# tank_adapter.net
KiCad netlist of a schematic drawn in Altium Designer
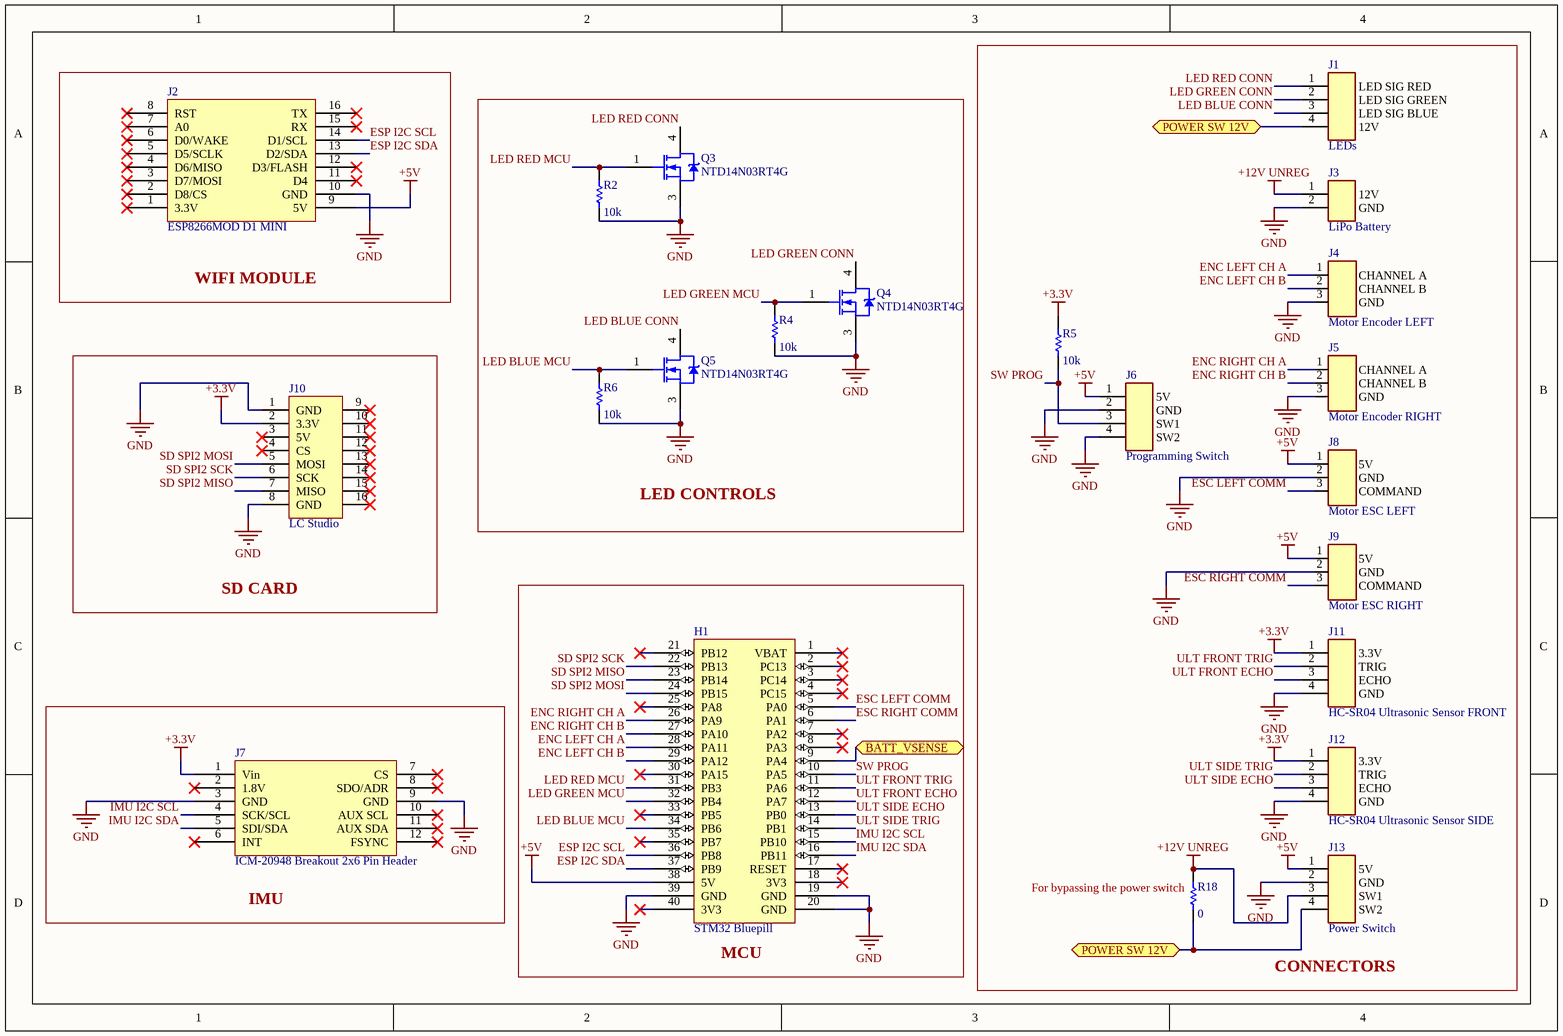
[diagram p0: tank_adapter.SchDoc]

(export (version "E")
  (design (tool "Eeschema 10.0.6"))
  (components
    (comp (ref "H1")
      (value "STM32 Bluepill")
      (footprint "STM32 Bluepill")
      (libsource (lib "Cell_Tester") (part "STM32 Bluepill"))
    )
    (comp (ref "J1")
      (value "LEDs")
      (footprint "HDRV4W85P254_4X1_1062X650X1000")
      (description "4 Position Wire to Board Terminal Block Horizontal with Board 0.100 _2.54mm_ Through Hole")
      (fields (field (name "MF") "TE Connectivity") (field (name "MP") "282834-4"))
      (libsource (lib "282834-4-1") (part "282834-4"))
    )
    (comp (ref "J2")
      (value "ESP8266MOD D1 MINI")
      (footprint "ESP8266MOD D1 MINI")
      (libsource (lib "MTE380_Lib") (part "ESP8266MOD D1 MINI"))
    )
    (comp (ref "J3")
      (value "LiPo Battery")
      (footprint "TE_282837-2")
      (description "Connector Terminal Blocks Receptacle 2 Position 5.08mm Solder Straight Thru-Hole 13.5A/Contact")
      (fields (field (name "MF") "TE Connectivity") (field (name "MP") "282837-2"))
      (libsource (lib "282837-2") (part "282837-2"))
    )
    (comp (ref "J4")
      (value "Motor Encoder LEFT")
      (footprint "TE_282834-3")
      (description "3 Position Wire to Board Terminal Block Horizontal with Board 0.100 (2.54mm)")
      (fields (field (name "MF") "TE Connectivity") (field (name "MP") "282834-3"))
      (libsource (lib "282834-3") (part "282834-3"))
    )
    (comp (ref "J5")
      (value "Motor Encoder RIGHT")
      (footprint "TE_282834-3")
      (description "3 Position Wire to Board Terminal Block Horizontal with Board 0.100 (2.54mm)")
      (fields (field (name "MF") "TE Connectivity") (field (name "MP") "282834-3"))
      (libsource (lib "282834-3") (part "282834-3"))
    )
    (comp (ref "J6")
      (value "Programming Switch")
      (footprint "HDRV4W85P254_4X1_1062X650X1000")
      (description "4 Position Wire to Board Terminal Block Horizontal with Board 0.100 _2.54mm_ Through Hole")
      (fields (field (name "MF") "TE Connectivity") (field (name "MP") "282834-4"))
      (libsource (lib "282834-4-1") (part "282834-4"))
    )
    (comp (ref "J7")
      (value "ICM-20948 Breakout 2x6 Pin Header")
      (footprint "ICM20948 Breakout")
      (description "THT Vertical Pin Header WR-PHD, Pitch 2.54 mm, Double Row, 2x6 pins")
      (libsource (lib "MTE380_Lib") (part "ICM-20948 Breakout 2x6 Pin Header"))
    )
    (comp (ref "J8")
      (value "Motor ESC LEFT")
      (footprint "TE_282834-3")
      (description "3 Position Wire to Board Terminal Block Horizontal with Board 0.100 (2.54mm)")
      (fields (field (name "MF") "TE Connectivity") (field (name "MP") "282834-3"))
      (libsource (lib "282834-3") (part "282834-3"))
    )
    (comp (ref "J9")
      (value "Motor ESC RIGHT")
      (footprint "TE_282834-3")
      (description "3 Position Wire to Board Terminal Block Horizontal with Board 0.100 (2.54mm)")
      (fields (field (name "MF") "TE Connectivity") (field (name "MP") "282834-3"))
      (libsource (lib "282834-3") (part "282834-3"))
    )
    (comp (ref "J10")
      (value "LC Studio")
      (footprint "HDR2X8_CEN")
      (description "Header, 8-Pin, Dual row")
      (fields (field (name "PUBLISHER") "Altium Limited"))
      (libsource (lib "Miscellaneous Connectors") (part "Header 8X2A"))
    )
    (comp (ref "J11")
      (value "HC-SR04 Ultrasonic Sensor FRONT")
      (footprint "HDRV4W85P254_4X1_1062X650X1000")
      (description "4 Position Wire to Board Terminal Block Horizontal with Board 0.100 _2.54mm_ Through Hole")
      (fields (field (name "MF") "TE Connectivity") (field (name "MP") "282834-4"))
      (libsource (lib "282834-4-1") (part "282834-4"))
    )
    (comp (ref "J12")
      (value "HC-SR04 Ultrasonic Sensor SIDE")
      (footprint "HDRV4W85P254_4X1_1062X650X1000")
      (description "4 Position Wire to Board Terminal Block Horizontal with Board 0.100 _2.54mm_ Through Hole")
      (fields (field (name "MF") "TE Connectivity") (field (name "MP") "282834-4"))
      (libsource (lib "282834-4-1") (part "282834-4"))
    )
    (comp (ref "J13")
      (value "Power Switch")
      (footprint "HDRV4W85P254_4X1_1062X650X1000")
      (description "4 Position Wire to Board Terminal Block Horizontal with Board 0.100 _2.54mm_ Through Hole")
      (fields (field (name "MF") "TE Connectivity") (field (name "MP") "282834-4"))
      (libsource (lib "282834-4-1") (part "282834-4"))
    )
    (comp (ref "Q3")
      (value "NTD14N03RT4G")
      (footprint "ONSC-DPAK-3-369C-01_V")
      (description "Power MOSFET, 14 A, 25 V, N-Channel, 3-Pin DPAK, Pb-Free, Tape and Reel")
      (fields (field (name "MANUFACTURER") "On Semiconductor"))
      (libsource (lib "Altium Content Vault") (part "ONSC-NMOS-G1S3D4-3_C"))
    )
    (comp (ref "Q4")
      (value "NTD14N03RT4G")
      (footprint "ONSC-DPAK-3-369C-01_V")
      (description "Power MOSFET, 14 A, 25 V, N-Channel, 3-Pin DPAK, Pb-Free, Tape and Reel")
      (fields (field (name "MANUFACTURER") "On Semiconductor"))
      (libsource (lib "Altium Content Vault") (part "ONSC-NMOS-G1S3D4-3_C"))
    )
    (comp (ref "Q5")
      (value "NTD14N03RT4G")
      (footprint "ONSC-DPAK-3-369C-01_V")
      (description "Power MOSFET, 14 A, 25 V, N-Channel, 3-Pin DPAK, Pb-Free, Tape and Reel")
      (fields (field (name "MANUFACTURER") "On Semiconductor"))
      (libsource (lib "Altium Content Vault") (part "ONSC-NMOS-G1S3D4-3_C"))
    )
    (comp (ref "R2")
      (value "10k")
      (footprint "6-0805_M")
      (description "Resistor")
      (fields (field (name "Comment") "Res1") (field (name "PUBLISHER") "Altium Limited"))
      (libsource (lib "Miscellaneous Devices") (part "Res1"))
    )
    (comp (ref "R4")
      (value "10k")
      (footprint "6-0805_M")
      (description "Resistor")
      (fields (field (name "Comment") "Res1") (field (name "PUBLISHER") "Altium Limited"))
      (libsource (lib "Miscellaneous Devices") (part "Res1"))
    )
    (comp (ref "R5")
      (value "10k")
      (footprint "6-0805_M")
      (description "Resistor")
      (fields (field (name "Comment") "Res1") (field (name "PUBLISHER") "Altium Limited"))
      (libsource (lib "Miscellaneous Devices") (part "Res1"))
    )
    (comp (ref "R6")
      (value "10k")
      (footprint "6-0805_M")
      (description "Resistor")
      (fields (field (name "Comment") "Res1") (field (name "PUBLISHER") "Altium Limited"))
      (libsource (lib "Miscellaneous Devices") (part "Res1"))
    )
    (comp (ref "R18")
      (value "0")
      (footprint "6-0805_M")
      (description "Resistor")
      (fields (field (name "Comment") "Res1") (field (name "PUBLISHER") "Altium Limited"))
      (libsource (lib "Miscellaneous Devices") (part "Res1"))
    )
  )
  (nets
    (net (code "1") (name "+3.3V") (class "Default")
      (node (ref "J10") (pin "2") (pinfunction "3.3V_2") (pintype "passive"))
      (node (ref "J11") (pin "1") (pinfunction "5V_1") (pintype "passive"))
      (node (ref "J12") (pin "1") (pinfunction "5V_1") (pintype "passive"))
      (node (ref "J7") (pin "1") (pinfunction "Vin_1") (pintype "passive"))
      (node (ref "R5") (pin "1") (pinfunction "1_1") (pintype "passive"))
    )
    (net (code "2") (name "+5V") (class "Default")
      (node (ref "H1") (pin "38") (pinfunction "5V_38") (pintype "power_in"))
      (node (ref "J13") (pin "1") (pinfunction "5V_1") (pintype "passive"))
      (node (ref "J2") (pin "9") (pinfunction "5V_9") (pintype "passive"))
      (node (ref "J6") (pin "1") (pinfunction "5V_1") (pintype "passive"))
      (node (ref "J8") (pin "1") (pinfunction "CHANNEL_A_1") (pintype "passive"))
      (node (ref "J9") (pin "1") (pinfunction "CHANNEL_A_1") (pintype "passive"))
    )
    (net (code "3") (name "+12V UNREG") (class "Default")
      (node (ref "J13") (pin "3") (pinfunction "SW1_3") (pintype "passive"))
      (node (ref "J3") (pin "1") (pinfunction "12V_1") (pintype "passive"))
      (node (ref "R18") (pin "1") (pinfunction "1_1") (pintype "passive"))
    )
    (net (code "4") (name "/BATT_VSENSE") (class "Default")
      (node (ref "H1") (pin "9") (pinfunction "PA4_9") (pintype "bidirectional"))
    )
    (net (code "5") (name "/ENC LEFT CH A") (class "Default")
      (node (ref "H1") (pin "28") (pinfunction "PA11_28") (pintype "bidirectional"))
      (node (ref "J4") (pin "1") (pinfunction "CHANNEL_A_1") (pintype "passive"))
    )
    (net (code "6") (name "/ENC LEFT CH B") (class "Default")
      (node (ref "H1") (pin "29") (pinfunction "PA12_29") (pintype "bidirectional"))
      (node (ref "J4") (pin "2") (pinfunction "CHANNEL_B_2") (pintype "passive"))
    )
    (net (code "7") (name "/ENC RIGHT CH A") (class "Default")
      (node (ref "H1") (pin "26") (pinfunction "PA9_26") (pintype "bidirectional"))
      (node (ref "J5") (pin "1") (pinfunction "CHANNEL_A_1") (pintype "passive"))
    )
    (net (code "8") (name "/ENC RIGHT CH B") (class "Default")
      (node (ref "H1") (pin "27") (pinfunction "PA10_27") (pintype "bidirectional"))
      (node (ref "J5") (pin "2") (pinfunction "CHANNEL_B_2") (pintype "passive"))
    )
    (net (code "9") (name "/ESC LEFT COMM") (class "Default")
      (node (ref "H1") (pin "5") (pinfunction "PA0_5") (pintype "bidirectional"))
      (node (ref "J8") (pin "3") (pinfunction "GND_3") (pintype "passive"))
    )
    (net (code "10") (name "/ESC RIGHT COMM") (class "Default")
      (node (ref "H1") (pin "6") (pinfunction "PA1_6") (pintype "bidirectional"))
      (node (ref "J9") (pin "3") (pinfunction "GND_3") (pintype "passive"))
    )
    (net (code "11") (name "/ESP I2C SCL") (class "Default")
      (node (ref "H1") (pin "36") (pinfunction "PB8_36") (pintype "bidirectional"))
      (node (ref "J2") (pin "14") (pinfunction "D1/SCL_14") (pintype "passive"))
    )
    (net (code "12") (name "/ESP I2C SDA") (class "Default")
      (node (ref "H1") (pin "37") (pinfunction "PB9_37") (pintype "bidirectional"))
      (node (ref "J2") (pin "13") (pinfunction "D2/SDA_13") (pintype "passive"))
    )
    (net (code "13") (name "/IMU I2C SCL") (class "Default")
      (node (ref "H1") (pin "15") (pinfunction "PB10_15") (pintype "bidirectional"))
      (node (ref "J7") (pin "4") (pinfunction "SCK/SCL_4") (pintype "passive"))
    )
    (net (code "14") (name "/IMU I2C SDA") (class "Default")
      (node (ref "H1") (pin "16") (pinfunction "PB11_16") (pintype "bidirectional"))
      (node (ref "J7") (pin "5") (pinfunction "SDI/SDA_5") (pintype "passive"))
    )
    (net (code "15") (name "/LED BLUE CONN") (class "Default")
      (node (ref "J1") (pin "3") (pinfunction "SW1_3") (pintype "passive"))
      (node (ref "Q5") (pin "4") (pinfunction "D_4") (pintype "passive"))
    )
    (net (code "16") (name "/LED BLUE MCU") (class "Default")
      (node (ref "H1") (pin "34") (pinfunction "PB6_34") (pintype "bidirectional"))
      (node (ref "Q5") (pin "1") (pinfunction "G_1") (pintype "passive"))
      (node (ref "R6") (pin "1") (pinfunction "1_1") (pintype "passive"))
    )
    (net (code "17") (name "/LED GREEN CONN") (class "Default")
      (node (ref "J1") (pin "2") (pinfunction "GND_2") (pintype "passive"))
      (node (ref "Q4") (pin "4") (pinfunction "D_4") (pintype "passive"))
    )
    (net (code "18") (name "/LED GREEN MCU") (class "Default")
      (node (ref "H1") (pin "32") (pinfunction "PB4_32") (pintype "bidirectional"))
      (node (ref "Q4") (pin "1") (pinfunction "G_1") (pintype "passive"))
      (node (ref "R4") (pin "1") (pinfunction "1_1") (pintype "passive"))
    )
    (net (code "19") (name "/LED RED CONN") (class "Default")
      (node (ref "J1") (pin "1") (pinfunction "5V_1") (pintype "passive"))
      (node (ref "Q3") (pin "4") (pinfunction "D_4") (pintype "passive"))
    )
    (net (code "20") (name "/LED RED MCU") (class "Default")
      (node (ref "H1") (pin "31") (pinfunction "PB3_31") (pintype "bidirectional"))
      (node (ref "Q3") (pin "1") (pinfunction "G_1") (pintype "passive"))
      (node (ref "R2") (pin "1") (pinfunction "1_1") (pintype "passive"))
    )
    (net (code "21") (name "/POWER SW 12V") (class "Default")
      (node (ref "J1") (pin "4") (pinfunction "SW2_4") (pintype "passive"))
      (node (ref "J13") (pin "4") (pinfunction "SW2_4") (pintype "passive"))
      (node (ref "R18") (pin "2") (pinfunction "2_2") (pintype "passive"))
    )
    (net (code "22") (name "/SD SPI2 MISO") (class "Default")
      (node (ref "H1") (pin "23") (pinfunction "PB14_23") (pintype "bidirectional"))
      (node (ref "J10") (pin "7") (pinfunction "MISO_7") (pintype "passive"))
    )
    (net (code "23") (name "/SD SPI2 MOSI") (class "Default")
      (node (ref "H1") (pin "24") (pinfunction "PB15_24") (pintype "bidirectional"))
      (node (ref "J10") (pin "5") (pinfunction "MOSI_5") (pintype "passive"))
    )
    (net (code "24") (name "/SD SPI2 SCK") (class "Default")
      (node (ref "H1") (pin "22") (pinfunction "PB13_22") (pintype "bidirectional"))
      (node (ref "J10") (pin "6") (pinfunction "SCK_6") (pintype "passive"))
    )
    (net (code "25") (name "/SW PROG") (class "Default")
      (node (ref "H1") (pin "10") (pinfunction "PA5_10") (pintype "bidirectional"))
      (node (ref "J6") (pin "3") (pinfunction "SW1_3") (pintype "passive"))
      (node (ref "R5") (pin "2") (pinfunction "2_2") (pintype "passive"))
    )
    (net (code "26") (name "/ULT FRONT ECHO") (class "Default")
      (node (ref "H1") (pin "12") (pinfunction "PA7_12") (pintype "bidirectional"))
      (node (ref "J11") (pin "3") (pinfunction "SW1_3") (pintype "passive"))
    )
    (net (code "27") (name "/ULT FRONT TRIG") (class "Default")
      (node (ref "H1") (pin "11") (pinfunction "PA6_11") (pintype "bidirectional"))
      (node (ref "J11") (pin "2") (pinfunction "GND_2") (pintype "passive"))
    )
    (net (code "28") (name "/ULT SIDE ECHO") (class "Default")
      (node (ref "H1") (pin "13") (pinfunction "PB0_13") (pintype "bidirectional"))
      (node (ref "J12") (pin "3") (pinfunction "SW1_3") (pintype "passive"))
    )
    (net (code "29") (name "/ULT SIDE TRIG") (class "Default")
      (node (ref "H1") (pin "14") (pinfunction "PB1_14") (pintype "bidirectional"))
      (node (ref "J12") (pin "2") (pinfunction "GND_2") (pintype "passive"))
    )
    (net (code "30") (name "GND") (class "Default")
      (node (ref "H1") (pin "19") (pinfunction "GND_19") (pintype "power_in"))
      (node (ref "H1") (pin "20") (pinfunction "GND_20") (pintype "power_in"))
      (node (ref "H1") (pin "39") (pinfunction "GND_39") (pintype "power_in"))
      (node (ref "J10") (pin "1") (pinfunction "GND_1") (pintype "passive"))
      (node (ref "J10") (pin "8") (pinfunction "GND_8") (pintype "passive"))
      (node (ref "J11") (pin "4") (pinfunction "SW2_4") (pintype "passive"))
      (node (ref "J12") (pin "4") (pinfunction "SW2_4") (pintype "passive"))
      (node (ref "J13") (pin "2") (pinfunction "GND_2") (pintype "passive"))
      (node (ref "J2") (pin "10") (pinfunction "GND_10") (pintype "passive"))
      (node (ref "J3") (pin "2") (pinfunction "GND_2") (pintype "passive"))
      (node (ref "J4") (pin "3") (pinfunction "GND_3") (pintype "passive"))
      (node (ref "J5") (pin "3") (pinfunction "GND_3") (pintype "passive"))
      (node (ref "J6") (pin "2") (pinfunction "GND_2") (pintype "passive"))
      (node (ref "J6") (pin "4") (pinfunction "SW2_4") (pintype "passive"))
      (node (ref "J7") (pin "3") (pinfunction "GND_3") (pintype "passive"))
      (node (ref "J7") (pin "9") (pinfunction "GND_9") (pintype "passive"))
      (node (ref "J8") (pin "2") (pinfunction "CHANNEL_B_2") (pintype "passive"))
      (node (ref "J9") (pin "2") (pinfunction "CHANNEL_B_2") (pintype "passive"))
      (node (ref "Q3") (pin "3") (pinfunction "S_3") (pintype "passive"))
      (node (ref "Q4") (pin "3") (pinfunction "S_3") (pintype "passive"))
      (node (ref "Q5") (pin "3") (pinfunction "S_3") (pintype "passive"))
      (node (ref "R2") (pin "2") (pinfunction "2_2") (pintype "passive"))
      (node (ref "R4") (pin "2") (pinfunction "2_2") (pintype "passive"))
      (node (ref "R6") (pin "2") (pinfunction "2_2") (pintype "passive"))
    )
    (net (code "31") (name "unconnected-(H1-3V3-Pad18)") (class "Default")
      (node (ref "H1") (pin "18") (pinfunction "3V3_18") (pintype "power_in+no_connect"))
    )
    (net (code "32") (name "unconnected-(H1-3V3-Pad40)") (class "Default")
      (node (ref "H1") (pin "40") (pinfunction "3V3_40") (pintype "power_in+no_connect"))
    )
    (net (code "33") (name "unconnected-(H1-PA2-Pad7)") (class "Default")
      (node (ref "H1") (pin "7") (pinfunction "PA2_7") (pintype "bidirectional+no_connect"))
    )
    (net (code "34") (name "unconnected-(H1-PA3-Pad8)") (class "Default")
      (node (ref "H1") (pin "8") (pinfunction "PA3_8") (pintype "bidirectional+no_connect"))
    )
    (net (code "35") (name "unconnected-(H1-PA8-Pad25)") (class "Default")
      (node (ref "H1") (pin "25") (pinfunction "PA8_25") (pintype "bidirectional+no_connect"))
    )
    (net (code "36") (name "unconnected-(H1-PA15-Pad30)") (class "Default")
      (node (ref "H1") (pin "30") (pinfunction "PA15_30") (pintype "bidirectional+no_connect"))
    )
    (net (code "37") (name "unconnected-(H1-PB5-Pad33)") (class "Default")
      (node (ref "H1") (pin "33") (pinfunction "PB5_33") (pintype "bidirectional+no_connect"))
    )
    (net (code "38") (name "unconnected-(H1-PB7-Pad35)") (class "Default")
      (node (ref "H1") (pin "35") (pinfunction "PB7_35") (pintype "bidirectional+no_connect"))
    )
    (net (code "39") (name "unconnected-(H1-PB12-Pad21)") (class "Default")
      (node (ref "H1") (pin "21") (pinfunction "PB12_21") (pintype "bidirectional+no_connect"))
    )
    (net (code "40") (name "unconnected-(H1-PC13-Pad2)") (class "Default")
      (node (ref "H1") (pin "2") (pinfunction "PC13_2") (pintype "bidirectional+no_connect"))
    )
    (net (code "41") (name "unconnected-(H1-PC14-Pad3)") (class "Default")
      (node (ref "H1") (pin "3") (pinfunction "PC14_3") (pintype "bidirectional+no_connect"))
    )
    (net (code "42") (name "unconnected-(H1-PC15-Pad4)") (class "Default")
      (node (ref "H1") (pin "4") (pinfunction "PC15_4") (pintype "bidirectional+no_connect"))
    )
    (net (code "43") (name "unconnected-(H1-RESET-Pad17)") (class "Default")
      (node (ref "H1") (pin "17") (pinfunction "RESET_17") (pintype "passive+no_connect"))
    )
    (net (code "44") (name "unconnected-(H1-VBAT-Pad1)") (class "Default")
      (node (ref "H1") (pin "1") (pinfunction "VBAT_1") (pintype "power_in+no_connect"))
    )
    (net (code "45") (name "unconnected-(J2-3.3V-Pad1)") (class "Default")
      (node (ref "J2") (pin "1") (pinfunction "3.3V_1") (pintype "passive+no_connect"))
    )
    (net (code "46") (name "unconnected-(J2-A0-Pad7)") (class "Default")
      (node (ref "J2") (pin "7") (pinfunction "A0_7") (pintype "passive+no_connect"))
    )
    (net (code "47") (name "unconnected-(J2-D0{slash}WAKE-Pad6)") (class "Default")
      (node (ref "J2") (pin "6") (pinfunction "D0/WAKE_6") (pintype "passive+no_connect"))
    )
    (net (code "48") (name "unconnected-(J2-D3{slash}FLASH-Pad12)") (class "Default")
      (node (ref "J2") (pin "12") (pinfunction "D3/FLASH_12") (pintype "passive+no_connect"))
    )
    (net (code "49") (name "unconnected-(J2-D4-Pad11)") (class "Default")
      (node (ref "J2") (pin "11") (pinfunction "D4_11") (pintype "passive+no_connect"))
    )
    (net (code "50") (name "unconnected-(J2-D5{slash}SCLK-Pad5)") (class "Default")
      (node (ref "J2") (pin "5") (pinfunction "D5/SCLK_5") (pintype "passive+no_connect"))
    )
    (net (code "51") (name "unconnected-(J2-D6{slash}MISO-Pad4)") (class "Default")
      (node (ref "J2") (pin "4") (pinfunction "D6/MISO_4") (pintype "passive+no_connect"))
    )
    (net (code "52") (name "unconnected-(J2-D7{slash}MOSI-Pad3)") (class "Default")
      (node (ref "J2") (pin "3") (pinfunction "D7/MOSI_3") (pintype "passive+no_connect"))
    )
    (net (code "53") (name "unconnected-(J2-D8{slash}CS-Pad2)") (class "Default")
      (node (ref "J2") (pin "2") (pinfunction "D8/CS_2") (pintype "passive+no_connect"))
    )
    (net (code "54") (name "unconnected-(J2-RST-Pad8)") (class "Default")
      (node (ref "J2") (pin "8") (pinfunction "RST_8") (pintype "passive+no_connect"))
    )
    (net (code "55") (name "unconnected-(J2-RX-Pad15)") (class "Default")
      (node (ref "J2") (pin "15") (pinfunction "RX_15") (pintype "passive+no_connect"))
    )
    (net (code "56") (name "unconnected-(J2-TX-Pad16)") (class "Default")
      (node (ref "J2") (pin "16") (pinfunction "TX_16") (pintype "passive+no_connect"))
    )
    (net (code "57") (name "unconnected-(J7-1.8V-Pad2)") (class "Default")
      (node (ref "J7") (pin "2") (pinfunction "1.8V_2") (pintype "passive+no_connect"))
    )
    (net (code "58") (name "unconnected-(J7-AUX_SCL-Pad10)") (class "Default")
      (node (ref "J7") (pin "10") (pinfunction "AUX_SCL_10") (pintype "passive+no_connect"))
    )
    (net (code "59") (name "unconnected-(J7-AUX_SDA-Pad11)") (class "Default")
      (node (ref "J7") (pin "11") (pinfunction "AUX_SDA_11") (pintype "passive+no_connect"))
    )
    (net (code "60") (name "unconnected-(J7-CS-Pad7)") (class "Default")
      (node (ref "J7") (pin "7") (pinfunction "CS_7") (pintype "passive+no_connect"))
    )
    (net (code "61") (name "unconnected-(J7-FSYNC-Pad12)") (class "Default")
      (node (ref "J7") (pin "12") (pinfunction "FSYNC_12") (pintype "passive+no_connect"))
    )
    (net (code "62") (name "unconnected-(J7-INT-Pad6)") (class "Default")
      (node (ref "J7") (pin "6") (pinfunction "INT_6") (pintype "passive+no_connect"))
    )
    (net (code "63") (name "unconnected-(J7-SDO{slash}ADR-Pad8)") (class "Default")
      (node (ref "J7") (pin "8") (pinfunction "SDO/ADR_8") (pintype "passive+no_connect"))
    )
    (net (code "64") (name "unconnected-(J10-5V-Pad3)") (class "Default")
      (node (ref "J10") (pin "3") (pinfunction "5V_3") (pintype "passive+no_connect"))
    )
    (net (code "65") (name "unconnected-(J10-CS-Pad4)") (class "Default")
      (node (ref "J10") (pin "4") (pinfunction "CS_4") (pintype "passive+no_connect"))
    )
    (net (code "66") (name "unconnected-(J10-Pad9)") (class "Default")
      (node (ref "J10") (pin "9") (pintype "passive+no_connect"))
    )
    (net (code "67") (name "unconnected-(J10-Pad10)") (class "Default")
      (node (ref "J10") (pin "10") (pintype "passive+no_connect"))
    )
    (net (code "68") (name "unconnected-(J10-Pad11)") (class "Default")
      (node (ref "J10") (pin "11") (pintype "passive+no_connect"))
    )
    (net (code "69") (name "unconnected-(J10-Pad12)") (class "Default")
      (node (ref "J10") (pin "12") (pintype "passive+no_connect"))
    )
    (net (code "70") (name "unconnected-(J10-Pad13)") (class "Default")
      (node (ref "J10") (pin "13") (pintype "passive+no_connect"))
    )
    (net (code "71") (name "unconnected-(J10-Pad14)") (class "Default")
      (node (ref "J10") (pin "14") (pintype "passive+no_connect"))
    )
    (net (code "72") (name "unconnected-(J10-Pad15)") (class "Default")
      (node (ref "J10") (pin "15") (pintype "passive+no_connect"))
    )
    (net (code "73") (name "unconnected-(J10-Pad16)") (class "Default")
      (node (ref "J10") (pin "16") (pintype "passive+no_connect"))
    )
  )
)
